# TZXDUINO.net
KiCad netlist of a schematic drawn in EAGLE
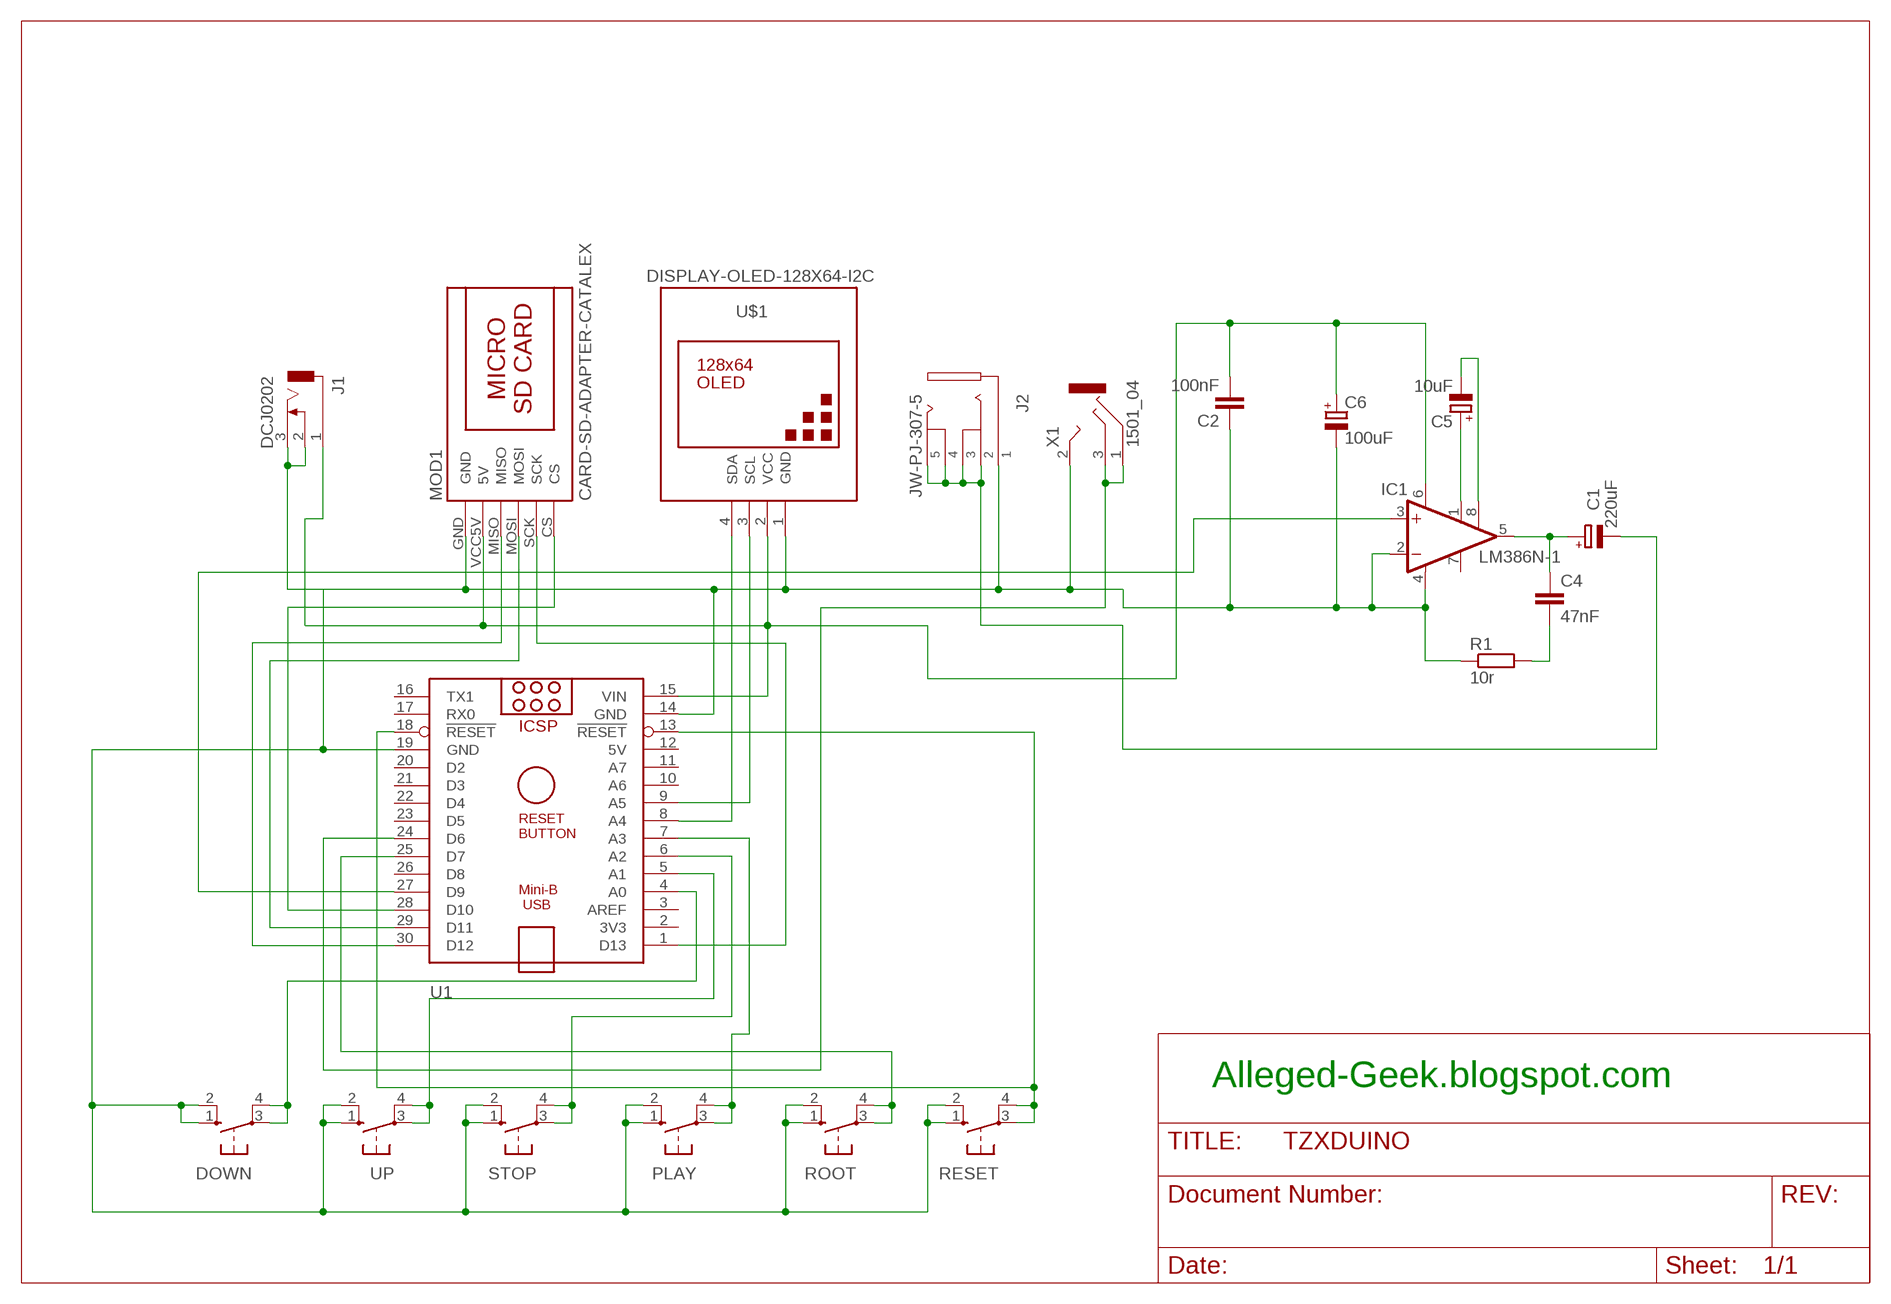
[diagram p0: schematic, sheet 1]

(export (version "E")
  (design (tool "Eeschema 10.0.6"))
  (components
    (comp (ref "C1")
      (value "220uF")
      (footprint "eagle-import:E3,5-8")
      (libsource (lib "eagle-import") (part "RGU-470UF-POLARCAP"))
    )
    (comp (ref "C2")
      (value "100nF")
      (footprint "eagle-import:C050-025X075")
      (libsource (lib "eagle-import") (part "RGU-CAPACITOR-CEU-50-25-75(100NF)"))
    )
    (comp (ref "C4")
      (value "47nF")
      (footprint "eagle-import:C050-025X075")
      (libsource (lib "eagle-import") (part "RGU-CAPACITOR-CEU-50-25-75(100NF)"))
    )
    (comp (ref "C5")
      (value "10uF")
      (footprint "eagle-import:E2,5-5")
      (libsource (lib "eagle-import") (part "RGU-10-100UF-POLARCAP"))
    )
    (comp (ref "C6")
      (value "100uF")
      (footprint "eagle-import:E2,5-5")
      (libsource (lib "eagle-import") (part "RGU-10-100UF-POLARCAP"))
    )
    (comp (ref "DOWN")
      (value "10-XX")
      (footprint "eagle-import:B3F-10XX")
      (fields (field (name "MPN") "B3F-1000"))
      (libsource (lib "eagle-import") (part "10-XX"))
    )
    (comp (ref "IC1")
      (value "LM386N-1")
      (footprint "eagle-import:DIL08")
      (libsource (lib "eagle-import") (part "LM386?-N1"))
    )
    (comp (ref "J1")
      (value "DCJ0202")
      (footprint "eagle-import:DCJ0202")
      (libsource (lib "eagle-import") (part "DCJ0202"))
    )
    (comp (ref "J2")
      (value "JW-PJ-307-5")
      (footprint "eagle-import:JW-PJ-307-5")
      (libsource (lib "eagle-import") (part "JW-PJ-307-5"))
    )
    (comp (ref "MOD1")
      (value "CARD-SD-ADAPTER-CATALEX")
      (footprint "eagle-import:CARD-SD-ADAPTER-CATALEX")
      (libsource (lib "eagle-import") (part "CARD-SD-ADAPTER-CATALEX"))
    )
    (comp (ref "PLAY")
      (value "10-XX")
      (footprint "eagle-import:B3F-10XX")
      (fields (field (name "MPN") "B3F-1000"))
      (libsource (lib "eagle-import") (part "10-XX"))
    )
    (comp (ref "R1")
      (value "10r")
      (footprint "eagle-import:0207_10")
      (libsource (lib "eagle-import") (part "RGU-RESISTOR-207/10"))
    )
    (comp (ref "RESET")
      (value "10-XX")
      (footprint "eagle-import:B3F-10XX")
      (fields (field (name "MPN") "B3F-1000"))
      (libsource (lib "eagle-import") (part "10-XX"))
    )
    (comp (ref "ROOT")
      (value "10-XX")
      (footprint "eagle-import:B3F-10XX")
      (fields (field (name "MPN") "B3F-1000"))
      (libsource (lib "eagle-import") (part "10-XX"))
    )
    (comp (ref "STOP")
      (value "10-XX")
      (footprint "eagle-import:B3F-10XX")
      (fields (field (name "MPN") "B3F-1000"))
      (libsource (lib "eagle-import") (part "10-XX"))
    )
    (comp (ref "U$1")
      (value "DISPLAY-OLED-128X64-I2C")
      (footprint "eagle-import:DISPLAY-OLED-128X64-I2C")
      (libsource (lib "eagle-import") (part "DISPLAY-OLED-128X64-I2C"))
    )
    (comp (ref "U1")
      (value "RGU-ARDUINONANO-SHIELD")
      (footprint "eagle-import:ARDUINO_NANO")
      (fields (field (name "MF") "Rapid") (field (name "MPN") "73-4448"))
      (libsource (lib "eagle-import") (part "RGU-ARDUINONANO-SHIELD"))
    )
    (comp (ref "UP")
      (value "10-XX")
      (footprint "eagle-import:B3F-10XX")
      (fields (field (name "MPN") "B3F-1000"))
      (libsource (lib "eagle-import") (part "10-XX"))
    )
    (comp (ref "X1")
      (value "1501_04")
      (footprint "eagle-import:1501_05")
      (libsource (lib "eagle-import") (part "1501_04"))
    )
  )
  (nets
    (net (code "1") (name "/5V") (class "Default")
      (node (ref "U1") (pin "12") (pinfunction "5V_12") (pintype "power_in"))
    )
    (net (code "2") (name "Net-(C1-Pad-)") (class "Default")
      (node (ref "C1") (pin "-") (pinfunction "-_-") (pintype "passive"))
      (node (ref "J2") (pin "2") (pinfunction "2_2") (pintype "passive"))
      (node (ref "J2") (pin "3") (pinfunction "3_3") (pintype "passive"))
      (node (ref "J2") (pin "4") (pinfunction "4_4") (pintype "passive"))
      (node (ref "J2") (pin "5") (pinfunction "5_5") (pintype "passive"))
    )
    (net (code "3") (name "Net-(C4-Pad2)") (class "Default")
      (node (ref "C4") (pin "2") (pinfunction "2_2") (pintype "passive"))
      (node (ref "R1") (pin "2") (pinfunction "2_2") (pintype "passive"))
    )
    (net (code "4") (name "Net-(C5-Pad+)") (class "Default")
      (node (ref "C5") (pin "+") (pinfunction "+_+") (pintype "passive"))
      (node (ref "IC1") (pin "1") (pinfunction "GAIN_1") (pintype "passive"))
    )
    (net (code "5") (name "Net-(C5-Pad-)") (class "Default")
      (node (ref "C5") (pin "-") (pinfunction "-_-") (pintype "passive"))
      (node (ref "IC1") (pin "8") (pinfunction "GAIN_8") (pintype "passive"))
    )
    (net (code "6") (name "Net-(DOWN-P)") (class "Default")
      (node (ref "DOWN") (pin "3") (pinfunction "P_3") (pintype "passive"))
      (node (ref "DOWN") (pin "4") (pinfunction "P1_4") (pintype "passive"))
      (node (ref "U1") (pin "4") (pinfunction "A0_4") (pintype "bidirectional"))
    )
    (net (code "7") (name "Net-(DOWN-S)") (class "Default")
      (node (ref "C2") (pin "1") (pinfunction "1_1") (pintype "passive"))
      (node (ref "C6") (pin "-") (pinfunction "-_-") (pintype "passive"))
      (node (ref "DOWN") (pin "1") (pinfunction "S_1") (pintype "passive"))
      (node (ref "DOWN") (pin "2") (pinfunction "S1_2") (pintype "passive"))
      (node (ref "IC1") (pin "2") (pinfunction "-IN_2") (pintype "input"))
      (node (ref "IC1") (pin "4") (pinfunction "GND_4") (pintype "power_in"))
      (node (ref "J1") (pin "2") (pinfunction "2_2") (pintype "passive"))
      (node (ref "J1") (pin "3") (pinfunction "3_3") (pintype "passive"))
      (node (ref "J2") (pin "1") (pinfunction "1_1") (pintype "passive"))
      (node (ref "MOD1") (pin "GND") (pinfunction "GND_GND") (pintype "power_in"))
      (node (ref "PLAY") (pin "1") (pinfunction "S_1") (pintype "passive"))
      (node (ref "PLAY") (pin "2") (pinfunction "S1_2") (pintype "passive"))
      (node (ref "R1") (pin "1") (pinfunction "1_1") (pintype "passive"))
      (node (ref "RESET") (pin "1") (pinfunction "S_1") (pintype "passive"))
      (node (ref "RESET") (pin "2") (pinfunction "S1_2") (pintype "passive"))
      (node (ref "ROOT") (pin "1") (pinfunction "S_1") (pintype "passive"))
      (node (ref "ROOT") (pin "2") (pinfunction "S1_2") (pintype "passive"))
      (node (ref "STOP") (pin "1") (pinfunction "S_1") (pintype "passive"))
      (node (ref "STOP") (pin "2") (pinfunction "S1_2") (pintype "passive"))
      (node (ref "U$1") (pin "1") (pinfunction "GND_1") (pintype "power_in"))
      (node (ref "U1") (pin "14") (pinfunction "GND_14") (pintype "power_in"))
      (node (ref "U1") (pin "19") (pinfunction "GND_19") (pintype "power_in"))
      (node (ref "UP") (pin "1") (pinfunction "S_1") (pintype "passive"))
      (node (ref "UP") (pin "2") (pinfunction "S1_2") (pintype "passive"))
      (node (ref "X1") (pin "2") (pinfunction "2_2") (pintype "passive"))
    )
    (net (code "8") (name "Net-(IC1-+IN)") (class "Default")
      (node (ref "IC1") (pin "3") (pinfunction "+IN_3") (pintype "input"))
      (node (ref "U1") (pin "27") (pinfunction "D9_27") (pintype "bidirectional"))
    )
    (net (code "9") (name "Net-(IC1-OUT)") (class "Default")
      (node (ref "C1") (pin "+") (pinfunction "+_+") (pintype "passive"))
      (node (ref "C4") (pin "1") (pinfunction "1_1") (pintype "passive"))
      (node (ref "IC1") (pin "5") (pinfunction "OUT_5") (pintype "output"))
    )
    (net (code "10") (name "Net-(IC1-VS)") (class "Default")
      (node (ref "C2") (pin "2") (pinfunction "2_2") (pintype "passive"))
      (node (ref "C6") (pin "+") (pinfunction "+_+") (pintype "passive"))
      (node (ref "IC1") (pin "6") (pinfunction "VS_6") (pintype "power_in"))
      (node (ref "J1") (pin "1") (pinfunction "1_1") (pintype "passive"))
      (node (ref "MOD1") (pin "VCC5V") (pinfunction "5V_VCC5V") (pintype "power_in"))
      (node (ref "U$1") (pin "2") (pinfunction "VCC_2") (pintype "power_in"))
      (node (ref "U1") (pin "15") (pinfunction "VIN_15") (pintype "power_in"))
    )
    (net (code "11") (name "Net-(PLAY-P)") (class "Default")
      (node (ref "PLAY") (pin "3") (pinfunction "P_3") (pintype "passive"))
      (node (ref "PLAY") (pin "4") (pinfunction "P1_4") (pintype "passive"))
      (node (ref "U1") (pin "7") (pinfunction "A3_7") (pintype "bidirectional"))
    )
    (net (code "12") (name "Net-(RESET-P)") (class "Default")
      (node (ref "RESET") (pin "3") (pinfunction "P_3") (pintype "passive"))
      (node (ref "RESET") (pin "4") (pinfunction "P1_4") (pintype "passive"))
      (node (ref "U1") (pin "13") (pinfunction "~{RESET}_13") (pintype "input"))
      (node (ref "U1") (pin "18") (pinfunction "~{RESET}_18") (pintype "input"))
    )
    (net (code "13") (name "Net-(ROOT-P)") (class "Default")
      (node (ref "ROOT") (pin "3") (pinfunction "P_3") (pintype "passive"))
      (node (ref "ROOT") (pin "4") (pinfunction "P1_4") (pintype "passive"))
      (node (ref "U1") (pin "25") (pinfunction "D7_25") (pintype "bidirectional"))
    )
    (net (code "14") (name "Net-(STOP-P)") (class "Default")
      (node (ref "STOP") (pin "3") (pinfunction "P_3") (pintype "passive"))
      (node (ref "STOP") (pin "4") (pinfunction "P1_4") (pintype "passive"))
      (node (ref "U1") (pin "6") (pinfunction "A2_6") (pintype "bidirectional"))
    )
    (net (code "15") (name "Net-(U$1-SCL)") (class "Default")
      (node (ref "U$1") (pin "3") (pinfunction "SCL_3") (pintype "bidirectional"))
      (node (ref "U1") (pin "9") (pinfunction "A5_9") (pintype "bidirectional"))
    )
    (net (code "16") (name "Net-(U$1-SDA)") (class "Default")
      (node (ref "U$1") (pin "4") (pinfunction "SDA_4") (pintype "bidirectional"))
      (node (ref "U1") (pin "8") (pinfunction "A4_8") (pintype "bidirectional"))
    )
    (net (code "17") (name "Net-(U1-A1)") (class "Default")
      (node (ref "U1") (pin "5") (pinfunction "A1_5") (pintype "bidirectional"))
      (node (ref "UP") (pin "3") (pinfunction "P_3") (pintype "passive"))
      (node (ref "UP") (pin "4") (pinfunction "P1_4") (pintype "passive"))
    )
    (net (code "18") (name "Net-(U1-D6)") (class "Default")
      (node (ref "U1") (pin "24") (pinfunction "D6_24") (pintype "bidirectional"))
      (node (ref "X1") (pin "1") (pinfunction "1_1") (pintype "passive"))
      (node (ref "X1") (pin "3") (pinfunction "3_3") (pintype "passive"))
    )
    (net (code "19") (name "Net-(U1-D10)") (class "Default")
      (node (ref "MOD1") (pin "CS") (pinfunction "CS_CS") (pintype "bidirectional"))
      (node (ref "U1") (pin "28") (pinfunction "D10_28") (pintype "bidirectional"))
    )
    (net (code "20") (name "Net-(U1-D11)") (class "Default")
      (node (ref "MOD1") (pin "MOSI") (pinfunction "MOSI_MOSI") (pintype "bidirectional"))
      (node (ref "U1") (pin "29") (pinfunction "D11_29") (pintype "bidirectional"))
    )
    (net (code "21") (name "Net-(U1-D12)") (class "Default")
      (node (ref "MOD1") (pin "MISO") (pinfunction "MISO_MISO") (pintype "bidirectional"))
      (node (ref "U1") (pin "30") (pinfunction "D12_30") (pintype "bidirectional"))
    )
    (net (code "22") (name "Net-(U1-D13)") (class "Default")
      (node (ref "MOD1") (pin "SCK") (pinfunction "SCK_SCK") (pintype "bidirectional"))
      (node (ref "U1") (pin "1") (pinfunction "D13_1") (pintype "bidirectional"))
    )
    (net (code "23") (name "unconnected-(IC1-BYPASS-Pad7)") (class "Default")
      (node (ref "IC1") (pin "7") (pinfunction "BYPASS_7") (pintype "passive"))
    )
    (net (code "24") (name "unconnected-(U1-3V3-Pad2)") (class "Default")
      (node (ref "U1") (pin "2") (pinfunction "3V3_2") (pintype "output"))
    )
    (net (code "25") (name "unconnected-(U1-A6-Pad10)") (class "Default")
      (node (ref "U1") (pin "10") (pinfunction "A6_10") (pintype "bidirectional"))
    )
    (net (code "26") (name "unconnected-(U1-A7-Pad11)") (class "Default")
      (node (ref "U1") (pin "11") (pinfunction "A7_11") (pintype "bidirectional"))
    )
    (net (code "27") (name "unconnected-(U1-AREF-Pad3)") (class "Default")
      (node (ref "U1") (pin "3") (pinfunction "AREF_3") (pintype "input"))
    )
    (net (code "28") (name "unconnected-(U1-D2-Pad20)") (class "Default")
      (node (ref "U1") (pin "20") (pinfunction "D2_20") (pintype "bidirectional"))
    )
    (net (code "29") (name "unconnected-(U1-D3-Pad21)") (class "Default")
      (node (ref "U1") (pin "21") (pinfunction "D3_21") (pintype "bidirectional"))
    )
    (net (code "30") (name "unconnected-(U1-D4-Pad22)") (class "Default")
      (node (ref "U1") (pin "22") (pinfunction "D4_22") (pintype "bidirectional"))
    )
    (net (code "31") (name "unconnected-(U1-D5-Pad23)") (class "Default")
      (node (ref "U1") (pin "23") (pinfunction "D5_23") (pintype "bidirectional"))
    )
    (net (code "32") (name "unconnected-(U1-D8-Pad26)") (class "Default")
      (node (ref "U1") (pin "26") (pinfunction "D8_26") (pintype "bidirectional"))
    )
    (net (code "33") (name "unconnected-(U1-RX0-Pad17)") (class "Default")
      (node (ref "U1") (pin "17") (pinfunction "RX0_17") (pintype "bidirectional"))
    )
    (net (code "34") (name "unconnected-(U1-TX1-Pad16)") (class "Default")
      (node (ref "U1") (pin "16") (pinfunction "TX1_16") (pintype "bidirectional"))
    )
  )
)
